# main.net
KiCad netlist of a schematic drawn in Altium Designer
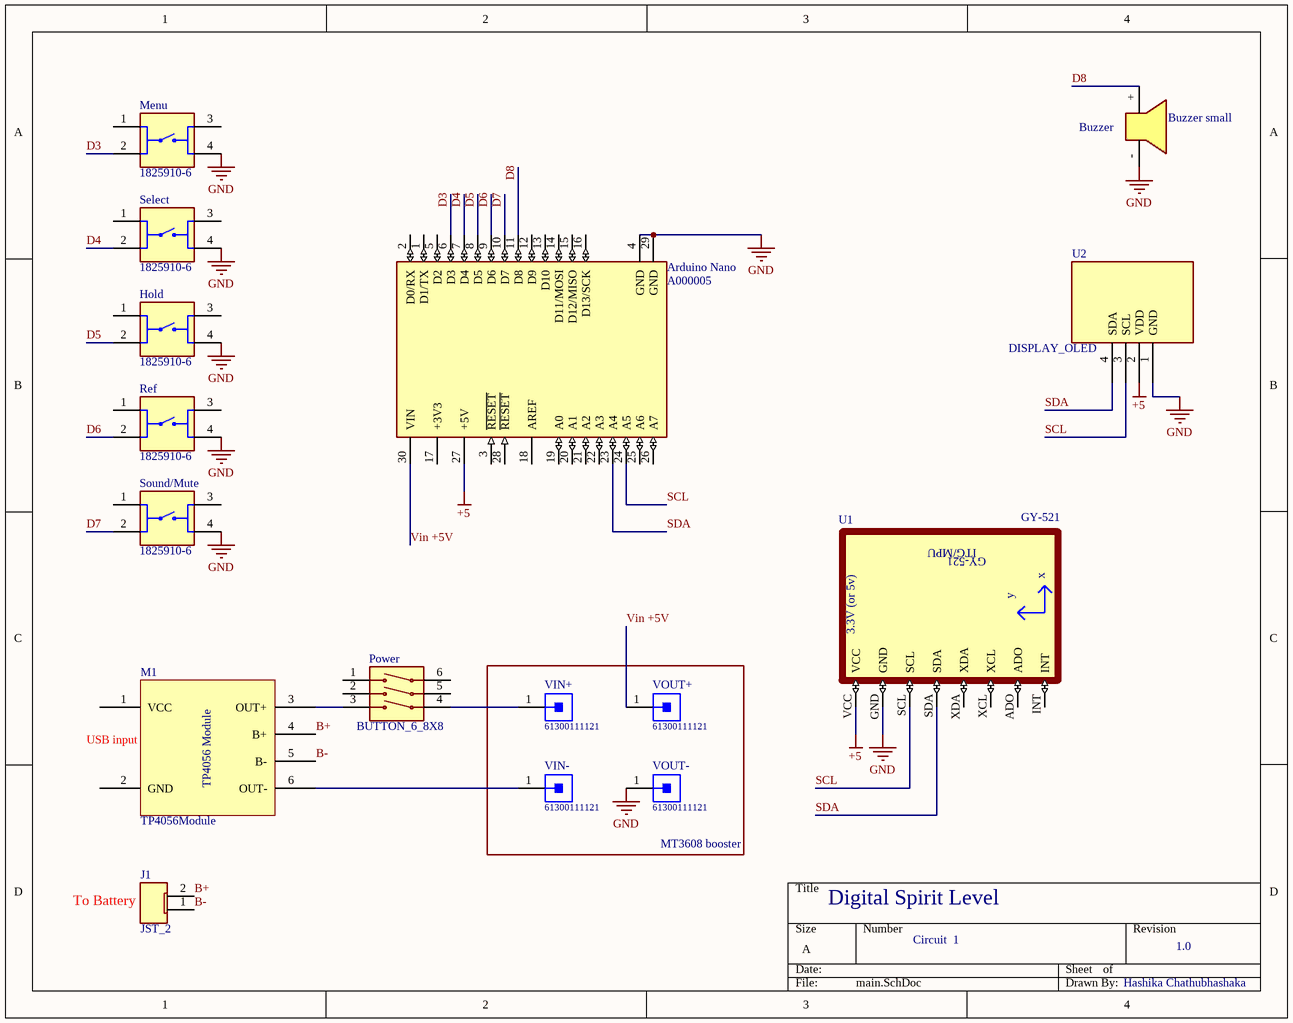
[diagram p0: main.SchDoc]

(export (version "E")
  (design (tool "Eeschema 10.0.6"))
  (components
    (comp (ref "Arduino Nano")
      (value "A000005")
      (footprint "FP-A000005-MFG")
      (description "ARDUINO NANO ATMEGA328 EVAL BRD")
      (libsource (lib "Altium Content Vault") (part "d190c066e99afd1c6882cf92e11b2cc"))
    )
    (comp (ref "Buzzer")
      (value "Buzzer small")
      (footprint "Buzzer")
      (description "5-12v small buzzer (12mm)")
      (libsource (lib "AYRIC Library") (part "Buzzer"))
    )
    (comp (ref "Hold")
      (value "1825910-6")
      (footprint "SW_1825910-6-4")
      (description "Switch Push Button OFF (ON) SPST Round Button 0.05A 24VDC Momentary Contact PC Pins Thru-Hole")
      (fields (field (name "MF") "TE Connectivity") (field (name "DIGI-KEY_PART_NUMBER") "450-1650-ND"))
      (libsource (lib "1825910-6") (part "1825910-6"))
    )
    (comp (ref "J1") (value "JST_2") (footprint "JST_2") (libsource (lib "Connectors") (part "JST_2")))
    (comp (ref "M1")
      (value "TP4056Module")
      (footprint "TP4056Module")
      (description "TP4056 Module for managing battery charging")
      (libsource (lib "Schlib1") (part "TP4056Module"))
    )
    (comp (ref "Menu")
      (value "1825910-6")
      (footprint "SW_1825910-6-4")
      (description "Switch Push Button OFF (ON) SPST Round Button 0.05A 24VDC Momentary Contact PC Pins Thru-Hole")
      (fields (field (name "MF") "TE Connectivity") (field (name "DIGI-KEY_PART_NUMBER") "450-1650-ND"))
      (libsource (lib "1825910-6") (part "1825910-6"))
    )
    (comp (ref "Power")
      (value "BUTTON_6_8X8")
      (footprint "BUTTON_6_8x8")
      (libsource (lib "Buttons & Switches") (part "BUTTON_6_8X8"))
    )
    (comp (ref "Ref")
      (value "1825910-6")
      (footprint "SW_1825910-6-4")
      (description "Switch Push Button OFF (ON) SPST Round Button 0.05A 24VDC Momentary Contact PC Pins Thru-Hole")
      (fields (field (name "MF") "TE Connectivity") (field (name "DIGI-KEY_PART_NUMBER") "450-1650-ND"))
      (libsource (lib "1825910-6") (part "1825910-6"))
    )
    (comp (ref "Select")
      (value "1825910-6")
      (footprint "SW_1825910-6-4")
      (description "Switch Push Button OFF (ON) SPST Round Button 0.05A 24VDC Momentary Contact PC Pins Thru-Hole")
      (fields (field (name "MF") "TE Connectivity") (field (name "DIGI-KEY_PART_NUMBER") "450-1650-ND"))
      (libsource (lib "1825910-6") (part "1825910-6"))
    )
    (comp (ref "Sound/Mute")
      (value "1825910-6")
      (footprint "SW_1825910-6-4")
      (description "Switch Push Button OFF (ON) SPST Round Button 0.05A 24VDC Momentary Contact PC Pins Thru-Hole")
      (fields (field (name "MF") "TE Connectivity") (field (name "DIGI-KEY_PART_NUMBER") "450-1650-ND"))
      (libsource (lib "1825910-6") (part "1825910-6"))
    )
    (comp (ref "U1")
      (value "GY-521")
      (footprint "GY-521")
      (description "Triple Axis Accelerometer Gyro Breakout")
      (fields (field (name "MF") "GODREAM FORDREAM CO., LIMITED"))
      (libsource (lib "GY-521") (part "GY-521"))
    )
    (comp (ref "U2")
      (value "DISPLAY_OLED")
      (footprint "DISPLAY_OLED")
      (libsource (lib "Displays") (part "DISPLAY_OLED"))
    )
    (comp (ref "VIN+")
      (value "61300111121")
      (footprint "61300111121")
      (description "THT Vertical Pin Header WR-PHD, Pitch 2.54 mm, Single Row, 1 pins")
      (fields (field (name "MANUFACTURER") "Wurth Elektronik") (field (name "PUBLISHER") "WurthElektronik"))
      (libsource (lib "Altium Content Vault") (part "WE-CN-1P-M-R1"))
    )
    (comp (ref "VIN-")
      (value "61300111121")
      (footprint "61300111121")
      (description "THT Vertical Pin Header WR-PHD, Pitch 2.54 mm, Single Row, 1 pins")
      (fields (field (name "MANUFACTURER") "Wurth Elektronik") (field (name "PUBLISHER") "WurthElektronik"))
      (libsource (lib "Altium Content Vault") (part "WE-CN-1P-M-R1"))
    )
    (comp (ref "VOUT+")
      (value "61300111121")
      (footprint "61300111121")
      (description "THT Vertical Pin Header WR-PHD, Pitch 2.54 mm, Single Row, 1 pins")
      (fields (field (name "MANUFACTURER") "Wurth Elektronik") (field (name "PUBLISHER") "WurthElektronik"))
      (libsource (lib "Altium Content Vault") (part "WE-CN-1P-M-R1"))
    )
    (comp (ref "VOUT-")
      (value "61300111121")
      (footprint "61300111121")
      (description "THT Vertical Pin Header WR-PHD, Pitch 2.54 mm, Single Row, 1 pins")
      (fields (field (name "MANUFACTURER") "Wurth Elektronik") (field (name "PUBLISHER") "WurthElektronik"))
      (libsource (lib "Altium Content Vault") (part "WE-CN-1P-M-R1"))
    )
  )
  (nets
    (net (code "1") (name "+5") (class "Default")
      (node (ref "Arduino Nano") (pin "27") (pinfunction "+5V_27") (pintype "power_in"))
      (node (ref "U1") (pin "VCC") (pinfunction "VCC_VCC") (pintype "bidirectional"))
      (node (ref "U2") (pin "2") (pinfunction "VDD_2") (pintype "tri_state"))
    )
    (net (code "2") (name "/B+") (class "Default")
      (node (ref "J1") (pin "2") (pintype "passive"))
      (node (ref "M1") (pin "4") (pinfunction "B+_4") (pintype "passive"))
    )
    (net (code "3") (name "/B-") (class "Default")
      (node (ref "J1") (pin "1") (pintype "passive"))
      (node (ref "M1") (pin "5") (pinfunction "B-_5") (pintype "passive"))
    )
    (net (code "4") (name "/D3") (class "Default")
      (node (ref "Arduino Nano") (pin "6") (pinfunction "D3_6") (pintype "bidirectional"))
      (node (ref "Menu") (pin "2") (pinfunction "2_2") (pintype "passive"))
    )
    (net (code "5") (name "/D4") (class "Default")
      (node (ref "Arduino Nano") (pin "7") (pinfunction "D4_7") (pintype "bidirectional"))
      (node (ref "Select") (pin "2") (pinfunction "2_2") (pintype "passive"))
    )
    (net (code "6") (name "/D5") (class "Default")
      (node (ref "Arduino Nano") (pin "8") (pinfunction "D5_8") (pintype "bidirectional"))
      (node (ref "Hold") (pin "2") (pinfunction "2_2") (pintype "passive"))
    )
    (net (code "7") (name "/D6") (class "Default")
      (node (ref "Arduino Nano") (pin "9") (pinfunction "D6_9") (pintype "bidirectional"))
      (node (ref "Ref") (pin "2") (pinfunction "2_2") (pintype "passive"))
    )
    (net (code "8") (name "/D7") (class "Default")
      (node (ref "Arduino Nano") (pin "10") (pinfunction "D7_10") (pintype "bidirectional"))
      (node (ref "Sound/Mute") (pin "2") (pinfunction "2_2") (pintype "passive"))
    )
    (net (code "9") (name "/D8") (class "Default")
      (node (ref "Arduino Nano") (pin "11") (pinfunction "D8_11") (pintype "bidirectional"))
      (node (ref "Buzzer") (pin "+") (pinfunction "1_+") (pintype "power_in"))
    )
    (net (code "10") (name "/SCL") (class "Default")
      (node (ref "Arduino Nano") (pin "24") (pinfunction "A5_24") (pintype "bidirectional"))
      (node (ref "U1") (pin "SCL") (pinfunction "SCL_SCL") (pintype "bidirectional"))
      (node (ref "U2") (pin "3") (pinfunction "SCL_3") (pintype "tri_state"))
    )
    (net (code "11") (name "/SDA") (class "Default")
      (node (ref "Arduino Nano") (pin "23") (pinfunction "A4_23") (pintype "bidirectional"))
      (node (ref "U1") (pin "SDA") (pinfunction "SDA_SDA") (pintype "bidirectional"))
      (node (ref "U2") (pin "4") (pinfunction "SDA_4") (pintype "tri_state"))
    )
    (net (code "12") (name "/Vin +5V") (class "Default")
      (node (ref "Arduino Nano") (pin "30") (pinfunction "VIN_30") (pintype "power_in"))
      (node (ref "VOUT+") (pin "1") (pinfunction "1_1") (pintype "passive"))
    )
    (net (code "13") (name "GND") (class "Default")
      (node (ref "Arduino Nano") (pin "29") (pinfunction "GND_29") (pintype "power_in"))
      (node (ref "Arduino Nano") (pin "4") (pinfunction "GND_4") (pintype "power_in"))
      (node (ref "Buzzer") (pin "-") (pinfunction "2_-") (pintype "power_in"))
      (node (ref "Hold") (pin "4") (pinfunction "4_4") (pintype "passive"))
      (node (ref "Menu") (pin "4") (pinfunction "4_4") (pintype "passive"))
      (node (ref "Ref") (pin "4") (pinfunction "4_4") (pintype "passive"))
      (node (ref "Select") (pin "4") (pinfunction "4_4") (pintype "passive"))
      (node (ref "Sound/Mute") (pin "4") (pinfunction "4_4") (pintype "passive"))
      (node (ref "U1") (pin "GND") (pinfunction "GND_GND") (pintype "bidirectional"))
      (node (ref "U2") (pin "1") (pinfunction "GND_1") (pintype "tri_state"))
      (node (ref "VOUT-") (pin "1") (pinfunction "1_1") (pintype "passive"))
    )
    (net (code "14") (name "Net-(M1-OUT+)") (class "Default")
      (node (ref "M1") (pin "3") (pinfunction "OUT+_3") (pintype "passive"))
      (node (ref "Power") (pin "3") (pinfunction "3_3") (pintype "passive"))
    )
    (net (code "15") (name "Net-(M1-OUT-)") (class "Default")
      (node (ref "M1") (pin "6") (pinfunction "OUT-_6") (pintype "passive"))
      (node (ref "VIN-") (pin "1") (pinfunction "1_1") (pintype "passive"))
    )
    (net (code "16") (name "Net-(Power-Pad4)") (class "Default")
      (node (ref "Power") (pin "4") (pinfunction "4_4") (pintype "passive"))
      (node (ref "VIN+") (pin "1") (pinfunction "1_1") (pintype "passive"))
    )
    (net (code "17") (name "unconnected-(Arduino Nano-+3V3-Pad17)") (class "Default")
      (node (ref "Arduino Nano") (pin "17") (pinfunction "+3V3_17") (pintype "power_in"))
    )
    (net (code "18") (name "unconnected-(Arduino Nano-A0-Pad19)") (class "Default")
      (node (ref "Arduino Nano") (pin "19") (pinfunction "A0_19") (pintype "bidirectional"))
    )
    (net (code "19") (name "unconnected-(Arduino Nano-A1-Pad20)") (class "Default")
      (node (ref "Arduino Nano") (pin "20") (pinfunction "A1_20") (pintype "bidirectional"))
    )
    (net (code "20") (name "unconnected-(Arduino Nano-A2-Pad21)") (class "Default")
      (node (ref "Arduino Nano") (pin "21") (pinfunction "A2_21") (pintype "bidirectional"))
    )
    (net (code "21") (name "unconnected-(Arduino Nano-A3-Pad22)") (class "Default")
      (node (ref "Arduino Nano") (pin "22") (pinfunction "A3_22") (pintype "bidirectional"))
    )
    (net (code "22") (name "unconnected-(Arduino Nano-A6-Pad25)") (class "Default")
      (node (ref "Arduino Nano") (pin "25") (pinfunction "A6_25") (pintype "bidirectional"))
    )
    (net (code "23") (name "unconnected-(Arduino Nano-A7-Pad26)") (class "Default")
      (node (ref "Arduino Nano") (pin "26") (pinfunction "A7_26") (pintype "bidirectional"))
    )
    (net (code "24") (name "unconnected-(Arduino Nano-AREF-Pad18)") (class "Default")
      (node (ref "Arduino Nano") (pin "18") (pinfunction "AREF_18") (pintype "passive"))
    )
    (net (code "25") (name "unconnected-(Arduino Nano-D0{slash}RX-Pad2)") (class "Default")
      (node (ref "Arduino Nano") (pin "2") (pinfunction "D0/RX_2") (pintype "bidirectional"))
    )
    (net (code "26") (name "unconnected-(Arduino Nano-D1{slash}TX-Pad1)") (class "Default")
      (node (ref "Arduino Nano") (pin "1") (pinfunction "D1/TX_1") (pintype "bidirectional"))
    )
    (net (code "27") (name "unconnected-(Arduino Nano-D2-Pad5)") (class "Default")
      (node (ref "Arduino Nano") (pin "5") (pinfunction "D2_5") (pintype "bidirectional"))
    )
    (net (code "28") (name "unconnected-(Arduino Nano-D9-Pad12)") (class "Default")
      (node (ref "Arduino Nano") (pin "12") (pinfunction "D9_12") (pintype "bidirectional"))
    )
    (net (code "29") (name "unconnected-(Arduino Nano-D10-Pad13)") (class "Default")
      (node (ref "Arduino Nano") (pin "13") (pinfunction "D10_13") (pintype "bidirectional"))
    )
    (net (code "30") (name "unconnected-(Arduino Nano-D11{slash}MOSI-Pad14)") (class "Default")
      (node (ref "Arduino Nano") (pin "14") (pinfunction "D11/MOSI_14") (pintype "bidirectional"))
    )
    (net (code "31") (name "unconnected-(Arduino Nano-D12{slash}MISO-Pad15)") (class "Default")
      (node (ref "Arduino Nano") (pin "15") (pinfunction "D12/MISO_15") (pintype "bidirectional"))
    )
    (net (code "32") (name "unconnected-(Arduino Nano-D13{slash}SCK-Pad16)") (class "Default")
      (node (ref "Arduino Nano") (pin "16") (pinfunction "D13/SCK_16") (pintype "bidirectional"))
    )
    (net (code "33") (name "unconnected-(Arduino Nano-~{RESET}-Pad3)") (class "Default")
      (node (ref "Arduino Nano") (pin "3") (pinfunction "~{RESET}_3") (pintype "input"))
    )
    (net (code "34") (name "unconnected-(Arduino Nano-~{RESET}-Pad28)") (class "Default")
      (node (ref "Arduino Nano") (pin "28") (pinfunction "~{RESET}_28") (pintype "input"))
    )
    (net (code "35") (name "unconnected-(Hold-Pad1)") (class "Default")
      (node (ref "Hold") (pin "1") (pinfunction "1_1") (pintype "passive"))
    )
    (net (code "36") (name "unconnected-(Hold-Pad3)") (class "Default")
      (node (ref "Hold") (pin "3") (pinfunction "3_3") (pintype "passive"))
    )
    (net (code "37") (name "unconnected-(M1-GND-Pad2)") (class "Default")
      (node (ref "M1") (pin "2") (pinfunction "GND_2") (pintype "passive"))
    )
    (net (code "38") (name "unconnected-(M1-VCC-Pad1)") (class "Default")
      (node (ref "M1") (pin "1") (pinfunction "VCC_1") (pintype "passive"))
    )
    (net (code "39") (name "unconnected-(Menu-Pad1)") (class "Default")
      (node (ref "Menu") (pin "1") (pinfunction "1_1") (pintype "passive"))
    )
    (net (code "40") (name "unconnected-(Menu-Pad3)") (class "Default")
      (node (ref "Menu") (pin "3") (pinfunction "3_3") (pintype "passive"))
    )
    (net (code "41") (name "unconnected-(Power-Pad1)") (class "Default")
      (node (ref "Power") (pin "1") (pinfunction "1_1") (pintype "passive"))
    )
    (net (code "42") (name "unconnected-(Power-Pad2)") (class "Default")
      (node (ref "Power") (pin "2") (pinfunction "2_2") (pintype "passive"))
    )
    (net (code "43") (name "unconnected-(Power-Pad5)") (class "Default")
      (node (ref "Power") (pin "5") (pinfunction "5_5") (pintype "passive"))
    )
    (net (code "44") (name "unconnected-(Power-Pad6)") (class "Default")
      (node (ref "Power") (pin "6") (pinfunction "6_6") (pintype "passive"))
    )
    (net (code "45") (name "unconnected-(Ref-Pad1)") (class "Default")
      (node (ref "Ref") (pin "1") (pinfunction "1_1") (pintype "passive"))
    )
    (net (code "46") (name "unconnected-(Ref-Pad3)") (class "Default")
      (node (ref "Ref") (pin "3") (pinfunction "3_3") (pintype "passive"))
    )
    (net (code "47") (name "unconnected-(Select-Pad1)") (class "Default")
      (node (ref "Select") (pin "1") (pinfunction "1_1") (pintype "passive"))
    )
    (net (code "48") (name "unconnected-(Select-Pad3)") (class "Default")
      (node (ref "Select") (pin "3") (pinfunction "3_3") (pintype "passive"))
    )
    (net (code "49") (name "unconnected-(Sound/Mute-Pad1)") (class "Default")
      (node (ref "Sound/Mute") (pin "1") (pinfunction "1_1") (pintype "passive"))
    )
    (net (code "50") (name "unconnected-(Sound/Mute-Pad3)") (class "Default")
      (node (ref "Sound/Mute") (pin "3") (pinfunction "3_3") (pintype "passive"))
    )
    (net (code "51") (name "unconnected-(U1-PadADO)") (class "Default")
      (node (ref "U1") (pin "ADO") (pinfunction "ADO_ADO") (pintype "bidirectional"))
    )
    (net (code "52") (name "unconnected-(U1-PadINT)") (class "Default")
      (node (ref "U1") (pin "INT") (pinfunction "INT_INT") (pintype "bidirectional"))
    )
    (net (code "53") (name "unconnected-(U1-PadXCL)") (class "Default")
      (node (ref "U1") (pin "XCL") (pinfunction "XCL_XCL") (pintype "bidirectional"))
    )
    (net (code "54") (name "unconnected-(U1-PadXDA)") (class "Default")
      (node (ref "U1") (pin "XDA") (pinfunction "XDA_XDA") (pintype "bidirectional"))
    )
  )
)
